# IR18T38.net
KiCad netlist of a schematic drawn in Altium Designer
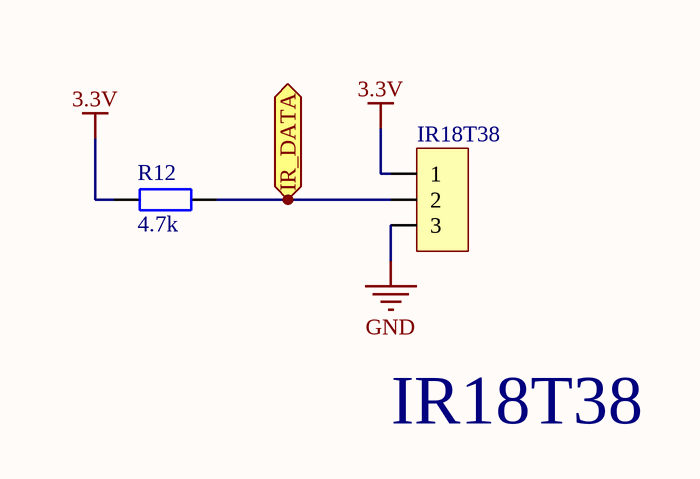
[diagram p0: IR18T38.SchDoc]

(export (version "E")
  (design (tool "Eeschema 10.0.6"))
  (components
    (comp (ref "IR18T38")
      (value "JP 1x3 2.54")
      (footprint "JP 1x3 CT")
      (description "Cắm")
      (libsource (lib "Altium_Lib_by_KhueNguyenCreator") (part "JP 1x3 2.54 Cai Thang"))
    )
    (comp (ref "R12")
      (value "4.7k")
      (footprint "tro smd 0603")
      (description "Dán")
      (libsource (lib "Altium_Lib_by_KhueNguyenCreator") (part "Tro 0603 5% 4.7k"))
    )
  )
  (nets
    (net (code "1") (name "/IR_DATA") (class "Default")
      (node (ref "IR18T38") (pin "2") (pinfunction "2_2") (pintype "passive"))
      (node (ref "R12") (pin "2") (pinfunction "2_2") (pintype "passive"))
    )
    (net (code "2") (name "3.3V") (class "Default")
      (node (ref "IR18T38") (pin "1") (pinfunction "1_1") (pintype "passive"))
      (node (ref "R12") (pin "1") (pinfunction "1_1") (pintype "passive"))
    )
    (net (code "3") (name "GND") (class "Default")
      (node (ref "IR18T38") (pin "3") (pinfunction "3_3") (pintype "passive"))
    )
  )
)
